# BumpSensors.net
KiCad netlist of a schematic drawn in Altium Designer
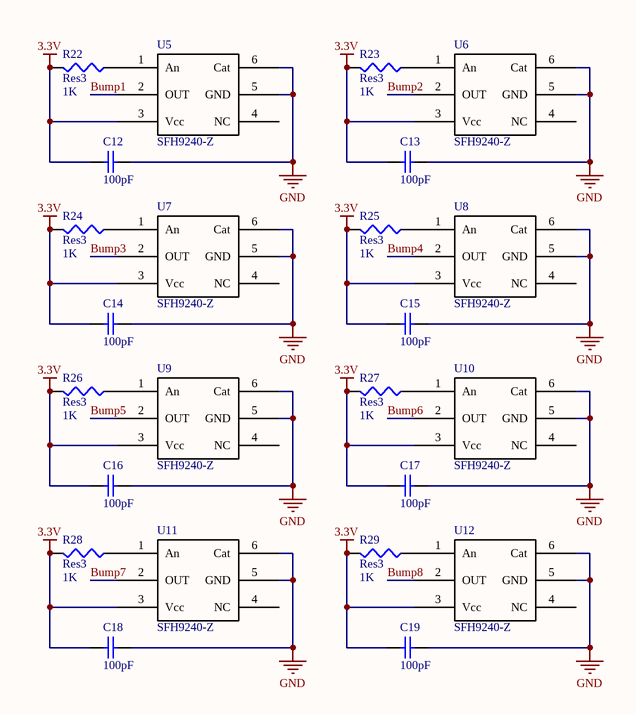
[diagram p0: BumpSensors.SchDoc]

(export (version "E")
  (design (tool "Eeschema 10.0.6"))
  (components
    (comp (ref "C12")
      (value "100pF")
      (footprint "CAPC1005L")
      (description "Capacitor (Semiconductor SIM Model)")
      (fields (field (name "Comment") "Cap Semi") (field (name "PUBLISHER") "Altium Limited"))
      (libsource (lib "Miscellaneous Devices") (part "Cap Semi"))
    )
    (comp (ref "C13")
      (value "100pF")
      (footprint "CAPC1005L")
      (description "Capacitor (Semiconductor SIM Model)")
      (fields (field (name "Comment") "Cap Semi") (field (name "PUBLISHER") "Altium Limited"))
      (libsource (lib "Miscellaneous Devices") (part "Cap Semi"))
    )
    (comp (ref "C14")
      (value "100pF")
      (footprint "CAPC1005L")
      (description "Capacitor (Semiconductor SIM Model)")
      (fields (field (name "Comment") "Cap Semi") (field (name "PUBLISHER") "Altium Limited"))
      (libsource (lib "Miscellaneous Devices") (part "Cap Semi"))
    )
    (comp (ref "C15")
      (value "100pF")
      (footprint "CAPC1005L")
      (description "Capacitor (Semiconductor SIM Model)")
      (fields (field (name "Comment") "Cap Semi") (field (name "PUBLISHER") "Altium Limited"))
      (libsource (lib "Miscellaneous Devices") (part "Cap Semi"))
    )
    (comp (ref "C16")
      (value "100pF")
      (footprint "CAPC1005L")
      (description "Capacitor (Semiconductor SIM Model)")
      (fields (field (name "Comment") "Cap Semi") (field (name "PUBLISHER") "Altium Limited"))
      (libsource (lib "Miscellaneous Devices") (part "Cap Semi"))
    )
    (comp (ref "C17")
      (value "100pF")
      (footprint "CAPC1005L")
      (description "Capacitor (Semiconductor SIM Model)")
      (fields (field (name "Comment") "Cap Semi") (field (name "PUBLISHER") "Altium Limited"))
      (libsource (lib "Miscellaneous Devices") (part "Cap Semi"))
    )
    (comp (ref "C18")
      (value "100pF")
      (footprint "CAPC1005L")
      (description "Capacitor (Semiconductor SIM Model)")
      (fields (field (name "Comment") "Cap Semi") (field (name "PUBLISHER") "Altium Limited"))
      (libsource (lib "Miscellaneous Devices") (part "Cap Semi"))
    )
    (comp (ref "C19")
      (value "100pF")
      (footprint "CAPC1005L")
      (description "Capacitor (Semiconductor SIM Model)")
      (fields (field (name "Comment") "Cap Semi") (field (name "PUBLISHER") "Altium Limited"))
      (libsource (lib "Miscellaneous Devices") (part "Cap Semi"))
    )
    (comp (ref "R22")
      (value "Res3")
      (footprint "RESC1608L")
      (description "Resistor")
      (fields (field (name "ALTIUM_VALUE") "1K") (field (name "PUBLISHER") "Altium Limited"))
      (libsource (lib "Miscellaneous Devices") (part "Res3"))
    )
    (comp (ref "R23")
      (value "Res3")
      (footprint "RESC1608L")
      (description "Resistor")
      (fields (field (name "ALTIUM_VALUE") "1K") (field (name "PUBLISHER") "Altium Limited"))
      (libsource (lib "Miscellaneous Devices") (part "Res3"))
    )
    (comp (ref "R24")
      (value "Res3")
      (footprint "RESC1608L")
      (description "Resistor")
      (fields (field (name "ALTIUM_VALUE") "1K") (field (name "PUBLISHER") "Altium Limited"))
      (libsource (lib "Miscellaneous Devices") (part "Res3"))
    )
    (comp (ref "R25")
      (value "Res3")
      (footprint "RESC1608L")
      (description "Resistor")
      (fields (field (name "ALTIUM_VALUE") "1K") (field (name "PUBLISHER") "Altium Limited"))
      (libsource (lib "Miscellaneous Devices") (part "Res3"))
    )
    (comp (ref "R26")
      (value "Res3")
      (footprint "RESC1608L")
      (description "Resistor")
      (fields (field (name "ALTIUM_VALUE") "1K") (field (name "PUBLISHER") "Altium Limited"))
      (libsource (lib "Miscellaneous Devices") (part "Res3"))
    )
    (comp (ref "R27")
      (value "Res3")
      (footprint "RESC1608L")
      (description "Resistor")
      (fields (field (name "ALTIUM_VALUE") "1K") (field (name "PUBLISHER") "Altium Limited"))
      (libsource (lib "Miscellaneous Devices") (part "Res3"))
    )
    (comp (ref "R28")
      (value "Res3")
      (footprint "RESC1608L")
      (description "Resistor")
      (fields (field (name "ALTIUM_VALUE") "1K") (field (name "PUBLISHER") "Altium Limited"))
      (libsource (lib "Miscellaneous Devices") (part "Res3"))
    )
    (comp (ref "R29")
      (value "Res3")
      (footprint "RESC1608L")
      (description "Resistor")
      (fields (field (name "ALTIUM_VALUE") "1K") (field (name "PUBLISHER") "Altium Limited"))
      (libsource (lib "Miscellaneous Devices") (part "Res3"))
    )
    (comp (ref "U5") (value "SFH9240-Z") (footprint "SFH9240-Z") (libsource (lib "mrone") (part "SFH9240-Z")))
    (comp (ref "U6") (value "SFH9240-Z") (footprint "SFH9240-Z") (libsource (lib "mrone") (part "SFH9240-Z")))
    (comp (ref "U7") (value "SFH9240-Z") (footprint "SFH9240-Z") (libsource (lib "mrone") (part "SFH9240-Z")))
    (comp (ref "U8") (value "SFH9240-Z") (footprint "SFH9240-Z") (libsource (lib "mrone") (part "SFH9240-Z")))
    (comp (ref "U9") (value "SFH9240-Z") (footprint "SFH9240-Z") (libsource (lib "mrone") (part "SFH9240-Z")))
    (comp (ref "U10")
      (value "SFH9240-Z")
      (footprint "SFH9240-Z")
      (libsource (lib "mrone") (part "SFH9240-Z"))
    )
    (comp (ref "U11")
      (value "SFH9240-Z")
      (footprint "SFH9240-Z")
      (libsource (lib "mrone") (part "SFH9240-Z"))
    )
    (comp (ref "U12")
      (value "SFH9240-Z")
      (footprint "SFH9240-Z")
      (libsource (lib "mrone") (part "SFH9240-Z"))
    )
  )
  (nets
    (net (code "1") (name "/Bump1") (class "Default")
      (node (ref "U5") (pin "2") (pinfunction "OUT_2") (pintype "passive"))
    )
    (net (code "2") (name "/Bump2") (class "Default")
      (node (ref "U6") (pin "2") (pinfunction "OUT_2") (pintype "passive"))
    )
    (net (code "3") (name "/Bump3") (class "Default")
      (node (ref "U7") (pin "2") (pinfunction "OUT_2") (pintype "passive"))
    )
    (net (code "4") (name "/Bump4") (class "Default")
      (node (ref "U8") (pin "2") (pinfunction "OUT_2") (pintype "passive"))
    )
    (net (code "5") (name "/Bump5") (class "Default")
      (node (ref "U9") (pin "2") (pinfunction "OUT_2") (pintype "passive"))
    )
    (net (code "6") (name "/Bump6") (class "Default")
      (node (ref "U10") (pin "2") (pinfunction "OUT_2") (pintype "passive"))
    )
    (net (code "7") (name "/Bump7") (class "Default")
      (node (ref "U11") (pin "2") (pinfunction "OUT_2") (pintype "passive"))
    )
    (net (code "8") (name "/Bump8") (class "Default")
      (node (ref "U12") (pin "2") (pinfunction "OUT_2") (pintype "passive"))
    )
    (net (code "9") (name "3.3V") (class "Default")
      (node (ref "C12") (pin "2") (pinfunction "2_2") (pintype "passive"))
      (node (ref "C13") (pin "2") (pinfunction "2_2") (pintype "passive"))
      (node (ref "C14") (pin "2") (pinfunction "2_2") (pintype "passive"))
      (node (ref "C15") (pin "2") (pinfunction "2_2") (pintype "passive"))
      (node (ref "C16") (pin "2") (pinfunction "2_2") (pintype "passive"))
      (node (ref "C17") (pin "2") (pinfunction "2_2") (pintype "passive"))
      (node (ref "C18") (pin "2") (pinfunction "2_2") (pintype "passive"))
      (node (ref "C19") (pin "2") (pinfunction "2_2") (pintype "passive"))
      (node (ref "R22") (pin "2") (pinfunction "2_2") (pintype "passive"))
      (node (ref "R23") (pin "2") (pinfunction "2_2") (pintype "passive"))
      (node (ref "R24") (pin "2") (pinfunction "2_2") (pintype "passive"))
      (node (ref "R25") (pin "2") (pinfunction "2_2") (pintype "passive"))
      (node (ref "R26") (pin "2") (pinfunction "2_2") (pintype "passive"))
      (node (ref "R27") (pin "2") (pinfunction "2_2") (pintype "passive"))
      (node (ref "R28") (pin "2") (pinfunction "2_2") (pintype "passive"))
      (node (ref "R29") (pin "2") (pinfunction "2_2") (pintype "passive"))
      (node (ref "U10") (pin "3") (pinfunction "Vcc_3") (pintype "passive"))
      (node (ref "U11") (pin "3") (pinfunction "Vcc_3") (pintype "passive"))
      (node (ref "U12") (pin "3") (pinfunction "Vcc_3") (pintype "passive"))
      (node (ref "U5") (pin "3") (pinfunction "Vcc_3") (pintype "passive"))
      (node (ref "U6") (pin "3") (pinfunction "Vcc_3") (pintype "passive"))
      (node (ref "U7") (pin "3") (pinfunction "Vcc_3") (pintype "passive"))
      (node (ref "U8") (pin "3") (pinfunction "Vcc_3") (pintype "passive"))
      (node (ref "U9") (pin "3") (pinfunction "Vcc_3") (pintype "passive"))
    )
    (net (code "10") (name "GND") (class "Default")
      (node (ref "C12") (pin "1") (pinfunction "1_1") (pintype "passive"))
      (node (ref "C13") (pin "1") (pinfunction "1_1") (pintype "passive"))
      (node (ref "C14") (pin "1") (pinfunction "1_1") (pintype "passive"))
      (node (ref "C15") (pin "1") (pinfunction "1_1") (pintype "passive"))
      (node (ref "C16") (pin "1") (pinfunction "1_1") (pintype "passive"))
      (node (ref "C17") (pin "1") (pinfunction "1_1") (pintype "passive"))
      (node (ref "C18") (pin "1") (pinfunction "1_1") (pintype "passive"))
      (node (ref "C19") (pin "1") (pinfunction "1_1") (pintype "passive"))
      (node (ref "U10") (pin "5") (pinfunction "GND_5") (pintype "passive"))
      (node (ref "U10") (pin "6") (pinfunction "Cat_6") (pintype "passive"))
      (node (ref "U11") (pin "5") (pinfunction "GND_5") (pintype "passive"))
      (node (ref "U11") (pin "6") (pinfunction "Cat_6") (pintype "passive"))
      (node (ref "U12") (pin "5") (pinfunction "GND_5") (pintype "passive"))
      (node (ref "U12") (pin "6") (pinfunction "Cat_6") (pintype "passive"))
      (node (ref "U5") (pin "5") (pinfunction "GND_5") (pintype "passive"))
      (node (ref "U5") (pin "6") (pinfunction "Cat_6") (pintype "passive"))
      (node (ref "U6") (pin "5") (pinfunction "GND_5") (pintype "passive"))
      (node (ref "U6") (pin "6") (pinfunction "Cat_6") (pintype "passive"))
      (node (ref "U7") (pin "5") (pinfunction "GND_5") (pintype "passive"))
      (node (ref "U7") (pin "6") (pinfunction "Cat_6") (pintype "passive"))
      (node (ref "U8") (pin "5") (pinfunction "GND_5") (pintype "passive"))
      (node (ref "U8") (pin "6") (pinfunction "Cat_6") (pintype "passive"))
      (node (ref "U9") (pin "5") (pinfunction "GND_5") (pintype "passive"))
      (node (ref "U9") (pin "6") (pinfunction "Cat_6") (pintype "passive"))
    )
    (net (code "11") (name "Net-(U5-An)") (class "Default")
      (node (ref "R22") (pin "1") (pinfunction "1_1") (pintype "passive"))
      (node (ref "U5") (pin "1") (pinfunction "An_1") (pintype "passive"))
    )
    (net (code "12") (name "Net-(U6-An)") (class "Default")
      (node (ref "R23") (pin "1") (pinfunction "1_1") (pintype "passive"))
      (node (ref "U6") (pin "1") (pinfunction "An_1") (pintype "passive"))
    )
    (net (code "13") (name "Net-(U7-An)") (class "Default")
      (node (ref "R24") (pin "1") (pinfunction "1_1") (pintype "passive"))
      (node (ref "U7") (pin "1") (pinfunction "An_1") (pintype "passive"))
    )
    (net (code "14") (name "Net-(U8-An)") (class "Default")
      (node (ref "R25") (pin "1") (pinfunction "1_1") (pintype "passive"))
      (node (ref "U8") (pin "1") (pinfunction "An_1") (pintype "passive"))
    )
    (net (code "15") (name "Net-(U9-An)") (class "Default")
      (node (ref "R26") (pin "1") (pinfunction "1_1") (pintype "passive"))
      (node (ref "U9") (pin "1") (pinfunction "An_1") (pintype "passive"))
    )
    (net (code "16") (name "Net-(U10-An)") (class "Default")
      (node (ref "R27") (pin "1") (pinfunction "1_1") (pintype "passive"))
      (node (ref "U10") (pin "1") (pinfunction "An_1") (pintype "passive"))
    )
    (net (code "17") (name "Net-(U11-An)") (class "Default")
      (node (ref "R28") (pin "1") (pinfunction "1_1") (pintype "passive"))
      (node (ref "U11") (pin "1") (pinfunction "An_1") (pintype "passive"))
    )
    (net (code "18") (name "Net-(U12-An)") (class "Default")
      (node (ref "R29") (pin "1") (pinfunction "1_1") (pintype "passive"))
      (node (ref "U12") (pin "1") (pinfunction "An_1") (pintype "passive"))
    )
    (net (code "19") (name "unconnected-(U5-NC-Pad4)") (class "Default")
      (node (ref "U5") (pin "4") (pinfunction "NC_4") (pintype "passive"))
    )
    (net (code "20") (name "unconnected-(U6-NC-Pad4)") (class "Default")
      (node (ref "U6") (pin "4") (pinfunction "NC_4") (pintype "passive"))
    )
    (net (code "21") (name "unconnected-(U7-NC-Pad4)") (class "Default")
      (node (ref "U7") (pin "4") (pinfunction "NC_4") (pintype "passive"))
    )
    (net (code "22") (name "unconnected-(U8-NC-Pad4)") (class "Default")
      (node (ref "U8") (pin "4") (pinfunction "NC_4") (pintype "passive"))
    )
    (net (code "23") (name "unconnected-(U9-NC-Pad4)") (class "Default")
      (node (ref "U9") (pin "4") (pinfunction "NC_4") (pintype "passive"))
    )
    (net (code "24") (name "unconnected-(U10-NC-Pad4)") (class "Default")
      (node (ref "U10") (pin "4") (pinfunction "NC_4") (pintype "passive"))
    )
    (net (code "25") (name "unconnected-(U11-NC-Pad4)") (class "Default")
      (node (ref "U11") (pin "4") (pinfunction "NC_4") (pintype "passive"))
    )
    (net (code "26") (name "unconnected-(U12-NC-Pad4)") (class "Default")
      (node (ref "U12") (pin "4") (pinfunction "NC_4") (pintype "passive"))
    )
  )
)
